# 40khz_ultrasonic_receiver_0_1.net
KiCad netlist of a schematic drawn in EAGLE
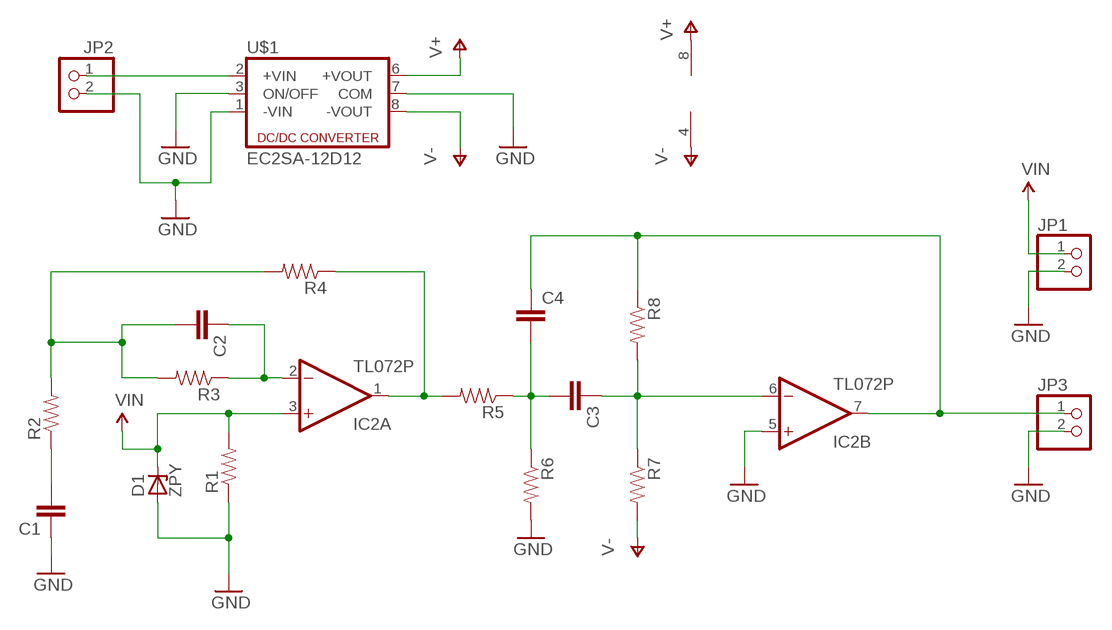
[diagram p0: schematic, sheet 1]

(export (version "E")
  (design (tool "Eeschema 10.0.6"))
  (components
    (comp (ref "C1")
      (value "CAPPTH")
      (footprint "eagle-import:CAP-PTH-SMALL")
      (libsource (lib "eagle-import") (part "CAPPTH"))
    )
    (comp (ref "C2")
      (value "CAPPTH")
      (footprint "eagle-import:CAP-PTH-SMALL")
      (libsource (lib "eagle-import") (part "CAPPTH"))
    )
    (comp (ref "C3")
      (value "CAPPTH")
      (footprint "eagle-import:CAP-PTH-SMALL")
      (libsource (lib "eagle-import") (part "CAPPTH"))
    )
    (comp (ref "C4")
      (value "CAPPTH")
      (footprint "eagle-import:CAP-PTH-SMALL")
      (libsource (lib "eagle-import") (part "CAPPTH"))
    )
    (comp (ref "D1")
      (value "ZPY")
      (footprint "eagle-import:DO41Z10")
      (libsource (lib "eagle-import") (part "ZPY"))
    )
    (comp (ref "IC2")
      (value "TL072P")
      (footprint "eagle-import:DIL08")
      (libsource (lib "eagle-import") (part "TL072P"))
    )
    (comp (ref "JP1")
      (value "PINHD-1X2")
      (footprint "eagle-import:1X02")
      (libsource (lib "eagle-import") (part "PINHD-1X2"))
    )
    (comp (ref "JP2")
      (value "PINHD-1X2")
      (footprint "eagle-import:1X02")
      (libsource (lib "eagle-import") (part "PINHD-1X2"))
    )
    (comp (ref "JP3")
      (value "PINHD-1X2")
      (footprint "eagle-import:1X02")
      (libsource (lib "eagle-import") (part "PINHD-1X2"))
    )
    (comp (ref "R1")
      (value "RESISTORPTH-1/4W")
      (footprint "eagle-import:AXIAL-0.4")
      (libsource (lib "eagle-import") (part "RESISTORPTH-1/4W"))
    )
    (comp (ref "R2")
      (value "RESISTORPTH-1/4W")
      (footprint "eagle-import:AXIAL-0.4")
      (libsource (lib "eagle-import") (part "RESISTORPTH-1/4W"))
    )
    (comp (ref "R3")
      (value "RESISTORPTH-1/4W")
      (footprint "eagle-import:AXIAL-0.4")
      (libsource (lib "eagle-import") (part "RESISTORPTH-1/4W"))
    )
    (comp (ref "R4")
      (value "RESISTORPTH-1/4W")
      (footprint "eagle-import:AXIAL-0.4")
      (libsource (lib "eagle-import") (part "RESISTORPTH-1/4W"))
    )
    (comp (ref "R5")
      (value "RESISTORPTH-1/4W")
      (footprint "eagle-import:AXIAL-0.4")
      (libsource (lib "eagle-import") (part "RESISTORPTH-1/4W"))
    )
    (comp (ref "R6")
      (value "RESISTORPTH-1/4W")
      (footprint "eagle-import:AXIAL-0.4")
      (libsource (lib "eagle-import") (part "RESISTORPTH-1/4W"))
    )
    (comp (ref "R7")
      (value "RESISTORPTH-1/4W")
      (footprint "eagle-import:AXIAL-0.4")
      (libsource (lib "eagle-import") (part "RESISTORPTH-1/4W"))
    )
    (comp (ref "R8")
      (value "RESISTORPTH-1/4W")
      (footprint "eagle-import:AXIAL-0.4")
      (libsource (lib "eagle-import") (part "RESISTORPTH-1/4W"))
    )
    (comp (ref "U$1")
      (value "EC2SA-12D12")
      (footprint "eagle-import:EC2SA")
      (libsource (lib "eagle-import") (part "EC2SA-12D12"))
    )
  )
  (nets
    (net (code "1") (name "GND") (class "Default")
      (node (ref "C1") (pin "1") (pinfunction "1_1") (pintype "passive"))
      (node (ref "D1") (pin "A") (pinfunction "A_A") (pintype "passive"))
      (node (ref "IC2") (pin "5") (pinfunction "+IN_5") (pintype "input"))
      (node (ref "JP1") (pin "2") (pinfunction "2_2") (pintype "passive"))
      (node (ref "JP2") (pin "2") (pinfunction "2_2") (pintype "passive"))
      (node (ref "JP3") (pin "2") (pinfunction "2_2") (pintype "passive"))
      (node (ref "R1") (pin "P$1") (pinfunction "1_P$1") (pintype "passive"))
      (node (ref "R6") (pin "P$2") (pinfunction "2_P$2") (pintype "passive"))
      (node (ref "U$1") (pin "1") (pinfunction "-VIN_1") (pintype "passive"))
      (node (ref "U$1") (pin "3") (pinfunction "ON/OFF_3") (pintype "passive"))
      (node (ref "U$1") (pin "7") (pinfunction "COM_7") (pintype "passive"))
    )
    (net (code "2") (name "Net-(IC2A--IN)") (class "Default")
      (node (ref "C2") (pin "1") (pinfunction "1_1") (pintype "passive"))
      (node (ref "IC2") (pin "2") (pinfunction "-IN_2") (pintype "input"))
      (node (ref "R3") (pin "P$1") (pinfunction "1_P$1") (pintype "passive"))
    )
    (net (code "3") (name "Net-(IC2A-OUT)") (class "Default")
      (node (ref "IC2") (pin "1") (pinfunction "OUT_1") (pintype "output"))
      (node (ref "R4") (pin "P$1") (pinfunction "1_P$1") (pintype "passive"))
      (node (ref "R5") (pin "P$2") (pinfunction "2_P$2") (pintype "passive"))
    )
    (net (code "4") (name "Net-(IC2B--IN)") (class "Default")
      (node (ref "C3") (pin "1") (pinfunction "1_1") (pintype "passive"))
      (node (ref "IC2") (pin "6") (pinfunction "-IN_6") (pintype "input"))
      (node (ref "R7") (pin "P$1") (pinfunction "1_P$1") (pintype "passive"))
      (node (ref "R8") (pin "P$2") (pinfunction "2_P$2") (pintype "passive"))
    )
    (net (code "5") (name "Net-(IC2B-OUT)") (class "Default")
      (node (ref "C4") (pin "1") (pinfunction "1_1") (pintype "passive"))
      (node (ref "IC2") (pin "7") (pinfunction "OUT_7") (pintype "output"))
      (node (ref "JP3") (pin "1") (pinfunction "1_1") (pintype "passive"))
      (node (ref "R8") (pin "P$1") (pinfunction "1_P$1") (pintype "passive"))
    )
    (net (code "6") (name "Net-(R2-1)") (class "Default")
      (node (ref "C1") (pin "2") (pinfunction "2_2") (pintype "passive"))
      (node (ref "R2") (pin "P$1") (pinfunction "1_P$1") (pintype "passive"))
    )
    (net (code "7") (name "Net-(R2-2)") (class "Default")
      (node (ref "C2") (pin "2") (pinfunction "2_2") (pintype "passive"))
      (node (ref "R2") (pin "P$2") (pinfunction "2_P$2") (pintype "passive"))
      (node (ref "R3") (pin "P$2") (pinfunction "2_P$2") (pintype "passive"))
      (node (ref "R4") (pin "P$2") (pinfunction "2_P$2") (pintype "passive"))
    )
    (net (code "8") (name "Net-(R5-1)") (class "Default")
      (node (ref "C3") (pin "2") (pinfunction "2_2") (pintype "passive"))
      (node (ref "C4") (pin "2") (pinfunction "2_2") (pintype "passive"))
      (node (ref "R5") (pin "P$1") (pinfunction "1_P$1") (pintype "passive"))
      (node (ref "R6") (pin "P$1") (pinfunction "1_P$1") (pintype "passive"))
    )
    (net (code "9") (name "Net-(U$1-+VIN)") (class "Default")
      (node (ref "JP2") (pin "1") (pinfunction "1_1") (pintype "passive"))
      (node (ref "U$1") (pin "2") (pinfunction "+VIN_2") (pintype "passive"))
    )
    (net (code "10") (name "V+") (class "Default")
      (node (ref "IC2") (pin "8") (pinfunction "V+_8") (pintype "power_in"))
      (node (ref "U$1") (pin "6") (pinfunction "+VOUT_6") (pintype "passive"))
    )
    (net (code "11") (name "V-") (class "Default")
      (node (ref "IC2") (pin "4") (pinfunction "V-_4") (pintype "power_in"))
      (node (ref "R7") (pin "P$2") (pinfunction "2_P$2") (pintype "passive"))
      (node (ref "U$1") (pin "8") (pinfunction "-VOUT_8") (pintype "passive"))
    )
    (net (code "12") (name "VIN") (class "Default")
      (node (ref "D1") (pin "C") (pinfunction "C_C") (pintype "passive"))
      (node (ref "IC2") (pin "3") (pinfunction "+IN_3") (pintype "input"))
      (node (ref "JP1") (pin "1") (pinfunction "1_1") (pintype "passive"))
      (node (ref "R1") (pin "P$2") (pinfunction "2_P$2") (pintype "passive"))
    )
  )
)
